# przetwornice5V_3V3_-5V.net
KiCad netlist of a schematic drawn in EAGLE
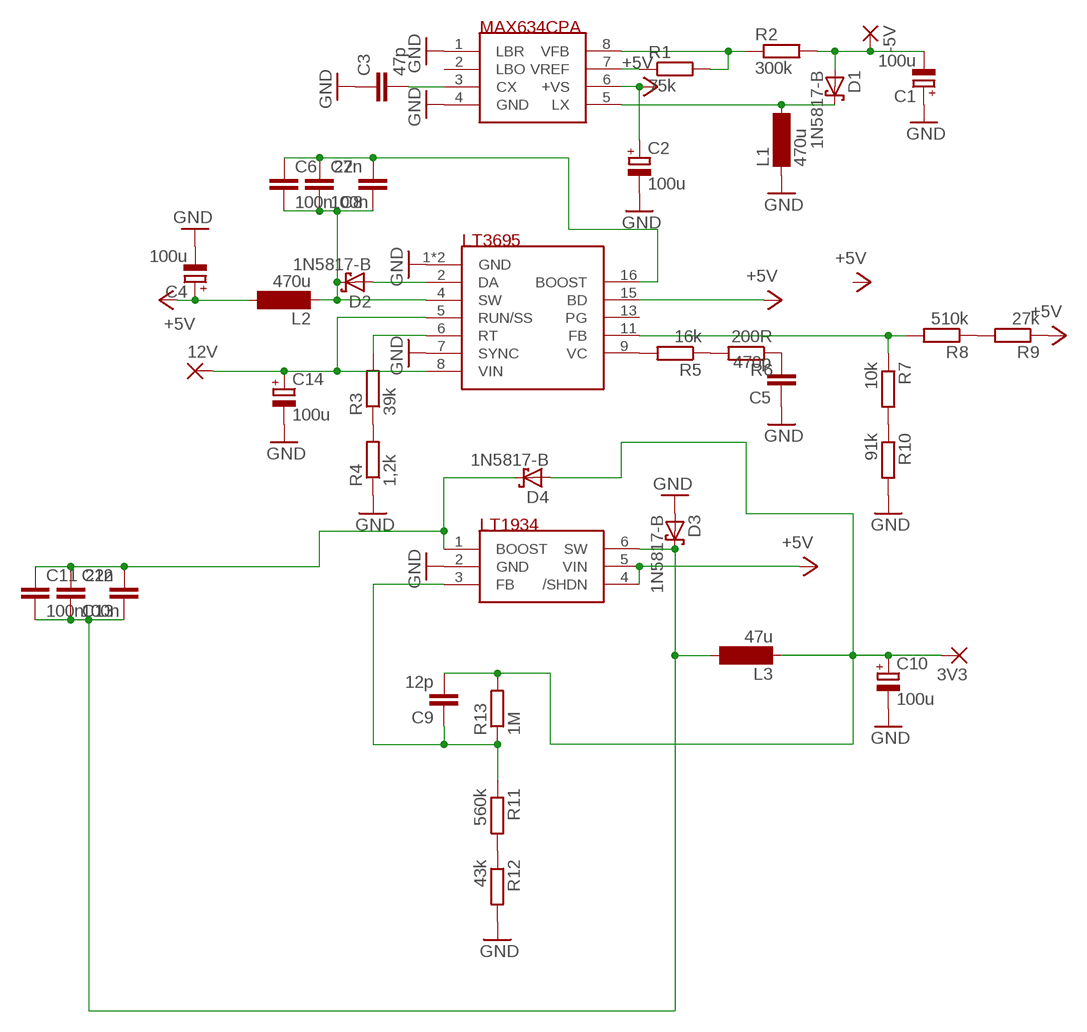
[diagram p0: schematic, sheet 1]

(export (version "E")
  (design (tool "Eeschema 10.0.6"))
  (components
    (comp (ref "-5V")
      (value "WIREPAD2,54/0,8")
      (footprint "eagle-import:2,54_0,8")
      (libsource (lib "eagle-import") (part "WIREPAD2,54/0,8"))
    )
    (comp (ref "3V3")
      (value "WIREPAD2,54/0,8")
      (footprint "eagle-import:2,54_0,8")
      (libsource (lib "eagle-import") (part "WIREPAD2,54/0,8"))
    )
    (comp (ref "12V")
      (value "WIREPAD2,54/0,8")
      (footprint "eagle-import:2,54_0,8")
      (libsource (lib "eagle-import") (part "WIREPAD2,54/0,8"))
    )
    (comp (ref "C1")
      (value "100u")
      (footprint "eagle-import:E2,5-7")
      (libsource (lib "eagle-import") (part "CPOL-EUE2.5-7"))
    )
    (comp (ref "C2")
      (value "100u")
      (footprint "eagle-import:E2,5-7")
      (libsource (lib "eagle-import") (part "CPOL-EUE2.5-7"))
    )
    (comp (ref "C3")
      (value "47p")
      (footprint "eagle-import:C2.5-2")
      (libsource (lib "eagle-import") (part "C2.5/2"))
    )
    (comp (ref "C4")
      (value "100u")
      (footprint "eagle-import:E2,5-7")
      (libsource (lib "eagle-import") (part "CPOL-EUE2.5-7"))
    )
    (comp (ref "C5")
      (value "470p")
      (footprint "eagle-import:C2.5-2")
      (libsource (lib "eagle-import") (part "C2.5/2"))
    )
    (comp (ref "C6")
      (value "100n")
      (footprint "eagle-import:C0805")
      (libsource (lib "eagle-import") (part "C-EUC0805"))
    )
    (comp (ref "C7")
      (value "100n")
      (footprint "eagle-import:C0805")
      (libsource (lib "eagle-import") (part "C-EUC0805"))
    )
    (comp (ref "C8")
      (value "22n")
      (footprint "eagle-import:C2.5-2")
      (libsource (lib "eagle-import") (part "C2.5/2"))
    )
    (comp (ref "C9")
      (value "12p")
      (footprint "eagle-import:C2.5-2")
      (libsource (lib "eagle-import") (part "C2.5/2"))
    )
    (comp (ref "C10")
      (value "100u")
      (footprint "eagle-import:E2,5-7")
      (libsource (lib "eagle-import") (part "CPOL-EUE2.5-7"))
    )
    (comp (ref "C11")
      (value "100n")
      (footprint "eagle-import:C0805")
      (libsource (lib "eagle-import") (part "C-EUC0805"))
    )
    (comp (ref "C12")
      (value "100n")
      (footprint "eagle-import:C0805")
      (libsource (lib "eagle-import") (part "C-EUC0805"))
    )
    (comp (ref "C13")
      (value "22n")
      (footprint "eagle-import:C2.5-2")
      (libsource (lib "eagle-import") (part "C2.5/2"))
    )
    (comp (ref "C14")
      (value "100u")
      (footprint "eagle-import:E2,5-7")
      (libsource (lib "eagle-import") (part "CPOL-EUE2.5-7"))
    )
    (comp (ref "D1")
      (value "1N5817-B")
      (footprint "eagle-import:DO41-7.6")
      (libsource (lib "eagle-import") (part "1N5817-B"))
    )
    (comp (ref "D2")
      (value "1N5817-B")
      (footprint "eagle-import:DO41-7.6")
      (libsource (lib "eagle-import") (part "1N5817-B"))
    )
    (comp (ref "D3")
      (value "1N5817-B")
      (footprint "eagle-import:DO41-7.6")
      (libsource (lib "eagle-import") (part "1N5817-B"))
    )
    (comp (ref "D4")
      (value "1N5817-B")
      (footprint "eagle-import:DO41-7.6")
      (libsource (lib "eagle-import") (part "1N5817-B"))
    )
    (comp (ref "L1")
      (value "470u")
      (footprint "eagle-import:MS50")
      (libsource (lib "eagle-import") (part "MS50"))
    )
    (comp (ref "L2")
      (value "470u")
      (footprint "eagle-import:MS50")
      (libsource (lib "eagle-import") (part "MS50"))
    )
    (comp (ref "L3")
      (value "47u")
      (footprint "eagle-import:MS50")
      (libsource (lib "eagle-import") (part "MS50"))
    )
    (comp (ref "R1")
      (value "75k")
      (footprint "eagle-import:R0805")
      (libsource (lib "eagle-import") (part "R-EU_R0805"))
    )
    (comp (ref "R2")
      (value "300k")
      (footprint "eagle-import:R0805")
      (libsource (lib "eagle-import") (part "R-EU_R0805"))
    )
    (comp (ref "R3")
      (value "39k")
      (footprint "eagle-import:R0805")
      (libsource (lib "eagle-import") (part "R-EU_R0805"))
    )
    (comp (ref "R4")
      (value "1,2k")
      (footprint "eagle-import:R0805")
      (libsource (lib "eagle-import") (part "R-EU_R0805"))
    )
    (comp (ref "R5")
      (value "16k")
      (footprint "eagle-import:R0805")
      (libsource (lib "eagle-import") (part "R-EU_R0805"))
    )
    (comp (ref "R6")
      (value "200R")
      (footprint "eagle-import:R0805")
      (libsource (lib "eagle-import") (part "R-EU_R0805"))
    )
    (comp (ref "R7")
      (value "10k")
      (footprint "eagle-import:R0805")
      (libsource (lib "eagle-import") (part "R-EU_R0805"))
    )
    (comp (ref "R8")
      (value "510k")
      (footprint "eagle-import:R0805")
      (libsource (lib "eagle-import") (part "R-EU_R0805"))
    )
    (comp (ref "R9")
      (value "27k")
      (footprint "eagle-import:R0805")
      (libsource (lib "eagle-import") (part "R-EU_R0805"))
    )
    (comp (ref "R10")
      (value "91k")
      (footprint "eagle-import:R0805")
      (libsource (lib "eagle-import") (part "R-EU_R0805"))
    )
    (comp (ref "R11")
      (value "560k")
      (footprint "eagle-import:R0805")
      (libsource (lib "eagle-import") (part "R-EU_R0805"))
    )
    (comp (ref "R12")
      (value "43k")
      (footprint "eagle-import:R0805")
      (libsource (lib "eagle-import") (part "R-EU_R0805"))
    )
    (comp (ref "R13")
      (value "1M")
      (footprint "eagle-import:0207_10")
      (libsource (lib "eagle-import") (part "R-EU_0207/10"))
    )
    (comp (ref "U$1")
      (value "MAX634CPA")
      (footprint "eagle-import:DIL08")
      (libsource (lib "eagle-import") (part "MAX634CPA"))
    )
    (comp (ref "U$2")
      (value "LT3695")
      (footprint "eagle-import:MSOP16")
      (libsource (lib "eagle-import") (part "LT3695"))
    )
    (comp (ref "U$3")
      (value "LT1934")
      (footprint "eagle-import:SOT23-6")
      (libsource (lib "eagle-import") (part "LT1934"))
    )
  )
  (nets
    (net (code "1") (name "+5V") (class "Default")
      (node (ref "C2") (pin "+") (pinfunction "+_+") (pintype "passive"))
      (node (ref "C4") (pin "+") (pinfunction "+_+") (pintype "passive"))
      (node (ref "L2") (pin "2") (pinfunction "2_2") (pintype "passive"))
      (node (ref "R9") (pin "1") (pinfunction "1_1") (pintype "passive"))
      (node (ref "U$1") (pin "6") (pinfunction "+VS_6") (pintype "bidirectional"))
      (node (ref "U$2") (pin "15") (pinfunction "BD_15") (pintype "bidirectional"))
      (node (ref "U$3") (pin "4") (pinfunction "/SHDN_4") (pintype "bidirectional"))
      (node (ref "U$3") (pin "5") (pinfunction "VIN_5") (pintype "bidirectional"))
    )
    (net (code "2") (name "GND") (class "Default")
      (node (ref "C1") (pin "+") (pinfunction "+_+") (pintype "passive"))
      (node (ref "C10") (pin "-") (pinfunction "-_-") (pintype "passive"))
      (node (ref "C14") (pin "-") (pinfunction "-_-") (pintype "passive"))
      (node (ref "C2") (pin "-") (pinfunction "-_-") (pintype "passive"))
      (node (ref "C3") (pin "1") (pinfunction "1_1") (pintype "passive"))
      (node (ref "C4") (pin "-") (pinfunction "-_-") (pintype "passive"))
      (node (ref "C5") (pin "1") (pinfunction "1_1") (pintype "passive"))
      (node (ref "D3") (pin "A") (pinfunction "A_A") (pintype "passive"))
      (node (ref "L1") (pin "1") (pinfunction "1_1") (pintype "passive"))
      (node (ref "R10") (pin "2") (pinfunction "2_2") (pintype "passive"))
      (node (ref "R12") (pin "2") (pinfunction "2_2") (pintype "passive"))
      (node (ref "R4") (pin "1") (pinfunction "1_1") (pintype "passive"))
      (node (ref "U$1") (pin "1") (pinfunction "LBR_1") (pintype "bidirectional"))
      (node (ref "U$1") (pin "4") (pinfunction "GND_4") (pintype "bidirectional"))
      (node (ref "U$2") (pin "1") (pinfunction "GND_1") (pintype "bidirectional"))
      (node (ref "U$2") (pin "14") (pinfunction "GND_14") (pintype "bidirectional"))
      (node (ref "U$2") (pin "7") (pinfunction "SYNC_7") (pintype "bidirectional"))
      (node (ref "U$3") (pin "2") (pinfunction "GND_2") (pintype "bidirectional"))
    )
    (net (code "3") (name "Net-(-5V-P)") (class "Default")
      (node (ref "-5V") (pin "1") (pinfunction "P_1") (pintype "passive"))
      (node (ref "C1") (pin "-") (pinfunction "-_-") (pintype "passive"))
      (node (ref "D1") (pin "A") (pinfunction "A_A") (pintype "passive"))
      (node (ref "R2") (pin "2") (pinfunction "2_2") (pintype "passive"))
    )
    (net (code "4") (name "Net-(3V3-P)") (class "Default")
      (node (ref "3V3") (pin "1") (pinfunction "P_1") (pintype "passive"))
      (node (ref "C10") (pin "+") (pinfunction "+_+") (pintype "passive"))
      (node (ref "C9") (pin "2") (pinfunction "2_2") (pintype "passive"))
      (node (ref "D4") (pin "A") (pinfunction "A_A") (pintype "passive"))
      (node (ref "L3") (pin "1") (pinfunction "1_1") (pintype "passive"))
      (node (ref "R13") (pin "2") (pinfunction "2_2") (pintype "passive"))
    )
    (net (code "5") (name "Net-(12V-P)") (class "Default")
      (node (ref "12V") (pin "1") (pinfunction "P_1") (pintype "passive"))
      (node (ref "C14") (pin "+") (pinfunction "+_+") (pintype "passive"))
      (node (ref "U$2") (pin "5") (pinfunction "RUN/SS_5") (pintype "bidirectional"))
      (node (ref "U$2") (pin "8") (pinfunction "VIN_8") (pintype "bidirectional"))
    )
    (net (code "6") (name "Net-(C5-Pad2)") (class "Default")
      (node (ref "C5") (pin "2") (pinfunction "2_2") (pintype "passive"))
      (node (ref "R6") (pin "1") (pinfunction "1_1") (pintype "passive"))
    )
    (net (code "7") (name "Net-(R3-Pad1)") (class "Default")
      (node (ref "R3") (pin "1") (pinfunction "1_1") (pintype "passive"))
      (node (ref "R4") (pin "2") (pinfunction "2_2") (pintype "passive"))
    )
    (net (code "8") (name "Net-(R5-Pad1)") (class "Default")
      (node (ref "R5") (pin "1") (pinfunction "1_1") (pintype "passive"))
      (node (ref "R6") (pin "2") (pinfunction "2_2") (pintype "passive"))
    )
    (net (code "9") (name "Net-(R8-Pad1)") (class "Default")
      (node (ref "R8") (pin "1") (pinfunction "1_1") (pintype "passive"))
      (node (ref "R9") (pin "2") (pinfunction "2_2") (pintype "passive"))
    )
    (net (code "10") (name "Net-(R10-Pad1)") (class "Default")
      (node (ref "R10") (pin "1") (pinfunction "1_1") (pintype "passive"))
      (node (ref "R7") (pin "2") (pinfunction "2_2") (pintype "passive"))
    )
    (net (code "11") (name "Net-(R11-Pad2)") (class "Default")
      (node (ref "R11") (pin "2") (pinfunction "2_2") (pintype "passive"))
      (node (ref "R12") (pin "1") (pinfunction "1_1") (pintype "passive"))
    )
    (net (code "12") (name "Net-(U$1-CX)") (class "Default")
      (node (ref "C3") (pin "2") (pinfunction "2_2") (pintype "passive"))
      (node (ref "U$1") (pin "3") (pinfunction "CX_3") (pintype "bidirectional"))
    )
    (net (code "13") (name "Net-(U$1-LX)") (class "Default")
      (node (ref "D1") (pin "C") (pinfunction "C_C") (pintype "passive"))
      (node (ref "L1") (pin "2") (pinfunction "2_2") (pintype "passive"))
      (node (ref "U$1") (pin "5") (pinfunction "LX_5") (pintype "bidirectional"))
    )
    (net (code "14") (name "Net-(U$1-VFB)") (class "Default")
      (node (ref "R1") (pin "2") (pinfunction "2_2") (pintype "passive"))
      (node (ref "R2") (pin "1") (pinfunction "1_1") (pintype "passive"))
      (node (ref "U$1") (pin "8") (pinfunction "VFB_8") (pintype "bidirectional"))
    )
    (net (code "15") (name "Net-(U$1-VREF)") (class "Default")
      (node (ref "R1") (pin "1") (pinfunction "1_1") (pintype "passive"))
      (node (ref "U$1") (pin "7") (pinfunction "VREF_7") (pintype "bidirectional"))
    )
    (net (code "16") (name "Net-(U$2-BOOST)") (class "Default")
      (node (ref "C6") (pin "1") (pinfunction "1_1") (pintype "passive"))
      (node (ref "C7") (pin "1") (pinfunction "1_1") (pintype "passive"))
      (node (ref "C8") (pin "2") (pinfunction "2_2") (pintype "passive"))
      (node (ref "U$2") (pin "16") (pinfunction "BOOST_16") (pintype "bidirectional"))
    )
    (net (code "17") (name "Net-(U$2-DA)") (class "Default")
      (node (ref "D2") (pin "A") (pinfunction "A_A") (pintype "passive"))
      (node (ref "U$2") (pin "2") (pinfunction "DA_2") (pintype "bidirectional"))
    )
    (net (code "18") (name "Net-(U$2-FB)") (class "Default")
      (node (ref "R7") (pin "1") (pinfunction "1_1") (pintype "passive"))
      (node (ref "R8") (pin "2") (pinfunction "2_2") (pintype "passive"))
      (node (ref "U$2") (pin "11") (pinfunction "FB_11") (pintype "bidirectional"))
    )
    (net (code "19") (name "Net-(U$2-RT)") (class "Default")
      (node (ref "R3") (pin "2") (pinfunction "2_2") (pintype "passive"))
      (node (ref "U$2") (pin "6") (pinfunction "RT_6") (pintype "bidirectional"))
    )
    (net (code "20") (name "Net-(U$2-SW)") (class "Default")
      (node (ref "C6") (pin "2") (pinfunction "2_2") (pintype "passive"))
      (node (ref "C7") (pin "2") (pinfunction "2_2") (pintype "passive"))
      (node (ref "C8") (pin "1") (pinfunction "1_1") (pintype "passive"))
      (node (ref "D2") (pin "C") (pinfunction "C_C") (pintype "passive"))
      (node (ref "L2") (pin "1") (pinfunction "1_1") (pintype "passive"))
      (node (ref "U$2") (pin "4") (pinfunction "SW_4") (pintype "bidirectional"))
    )
    (net (code "21") (name "Net-(U$2-VC)") (class "Default")
      (node (ref "R5") (pin "2") (pinfunction "2_2") (pintype "passive"))
      (node (ref "U$2") (pin "9") (pinfunction "VC_9") (pintype "bidirectional"))
    )
    (net (code "22") (name "Net-(U$3-BOOST)") (class "Default")
      (node (ref "C11") (pin "1") (pinfunction "1_1") (pintype "passive"))
      (node (ref "C12") (pin "1") (pinfunction "1_1") (pintype "passive"))
      (node (ref "C13") (pin "2") (pinfunction "2_2") (pintype "passive"))
      (node (ref "D4") (pin "C") (pinfunction "C_C") (pintype "passive"))
      (node (ref "U$3") (pin "1") (pinfunction "BOOST_1") (pintype "bidirectional"))
    )
    (net (code "23") (name "Net-(U$3-FB)") (class "Default")
      (node (ref "C9") (pin "1") (pinfunction "1_1") (pintype "passive"))
      (node (ref "R11") (pin "1") (pinfunction "1_1") (pintype "passive"))
      (node (ref "R13") (pin "1") (pinfunction "1_1") (pintype "passive"))
      (node (ref "U$3") (pin "3") (pinfunction "FB_3") (pintype "bidirectional"))
    )
    (net (code "24") (name "Net-(U$3-SW)") (class "Default")
      (node (ref "C11") (pin "2") (pinfunction "2_2") (pintype "passive"))
      (node (ref "C12") (pin "2") (pinfunction "2_2") (pintype "passive"))
      (node (ref "C13") (pin "1") (pinfunction "1_1") (pintype "passive"))
      (node (ref "D3") (pin "C") (pinfunction "C_C") (pintype "passive"))
      (node (ref "L3") (pin "2") (pinfunction "2_2") (pintype "passive"))
      (node (ref "U$3") (pin "6") (pinfunction "SW_6") (pintype "bidirectional"))
    )
    (net (code "25") (name "unconnected-(U$1-LBO-Pad2)") (class "Default")
      (node (ref "U$1") (pin "2") (pinfunction "LBO_2") (pintype "bidirectional"))
    )
    (net (code "26") (name "unconnected-(U$2-PG-Pad13)") (class "Default")
      (node (ref "U$2") (pin "13") (pinfunction "PG_13") (pintype "bidirectional"))
    )
  )
)
